# light.net
KiCad netlist of a schematic drawn in EAGLE
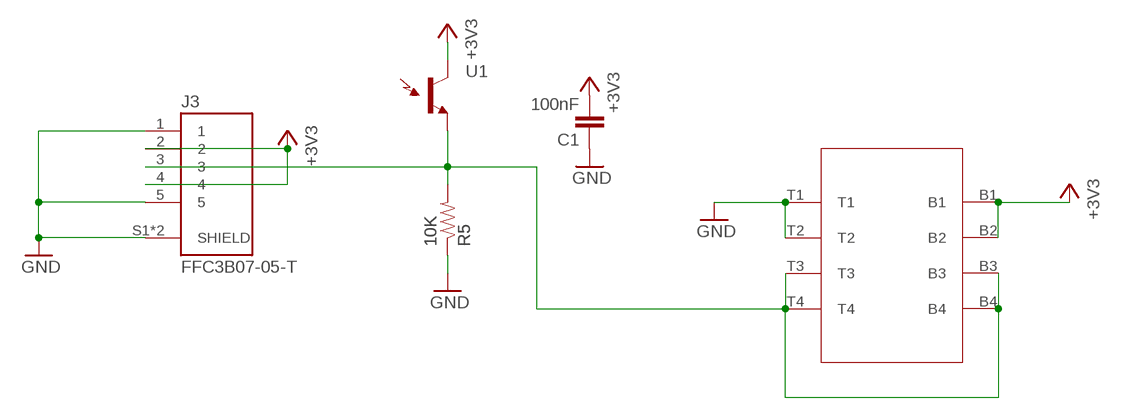
[diagram p0: schematic, sheet 1]

(export (version "E")
  (design (tool "Eeschema 10.0.6"))
  (components
    (comp (ref "C1")
      (value "100nF")
      (footprint "eagle-import:0805")
      (libsource (lib "eagle-import") (part "CAP0805"))
    )
    (comp (ref "J3")
      (value "FFC3B07-05-T")
      (footprint "eagle-import:GCT_FFC3B07-05-T")
      (fields (field (name "MF") "Global Connector Technology"))
      (libsource (lib "eagle-import") (part "FFC3B07-05-T"))
    )
    (comp (ref "R5")
      (value "10K")
      (footprint "eagle-import:0805")
      (libsource (lib "eagle-import") (part "RESISTOR0805-RES"))
    )
    (comp (ref "U$1")
      (value "LS_VERT")
      (footprint "eagle-import:LS_VERT")
      (libsource (lib "eagle-import") (part "LS_VERT"))
    )
    (comp (ref "U1")
      (value "TEMT6000")
      (footprint "eagle-import:TEMT6000-SEN")
      (libsource (lib "eagle-import") (part "TEMT6000"))
    )
  )
  (nets
    (net (code "1") (name "+3V3") (class "Default")
      (node (ref "C1") (pin "2") (pinfunction "2_2") (pintype "passive"))
      (node (ref "J3") (pin "2") (pinfunction "2_2") (pintype "passive"))
      (node (ref "J3") (pin "4") (pinfunction "4_4") (pintype "passive"))
      (node (ref "U$1") (pin "B1") (pinfunction "B1_B1") (pintype "bidirectional"))
      (node (ref "U$1") (pin "B2") (pinfunction "B2_B2") (pintype "bidirectional"))
      (node (ref "U1") (pin "COLLECTOR") (pinfunction "C1_COLLECTOR") (pintype "passive"))
    )
    (net (code "2") (name "GND") (class "Default")
      (node (ref "C1") (pin "1") (pinfunction "1_1") (pintype "passive"))
      (node (ref "J3") (pin "1") (pinfunction "1_1") (pintype "passive"))
      (node (ref "J3") (pin "5") (pinfunction "5_5") (pintype "passive"))
      (node (ref "J3") (pin "S1") (pinfunction "SHIELD_S1") (pintype "passive"))
      (node (ref "J3") (pin "S2") (pinfunction "SHIELD_S2") (pintype "passive"))
      (node (ref "R5") (pin "1") (pinfunction "1_1") (pintype "passive"))
      (node (ref "U$1") (pin "T1") (pinfunction "T1_T1") (pintype "bidirectional"))
      (node (ref "U$1") (pin "T2") (pinfunction "T2_T2") (pintype "bidirectional"))
    )
    (net (code "3") (name "Net-(U1-E1)") (class "Default")
      (node (ref "J3") (pin "3") (pinfunction "3_3") (pintype "passive"))
      (node (ref "R5") (pin "2") (pinfunction "2_2") (pintype "passive"))
      (node (ref "U$1") (pin "B3") (pinfunction "B3_B3") (pintype "bidirectional"))
      (node (ref "U$1") (pin "B4") (pinfunction "B4_B4") (pintype "bidirectional"))
      (node (ref "U$1") (pin "T3") (pinfunction "T3_T3") (pintype "bidirectional"))
      (node (ref "U$1") (pin "T4") (pinfunction "T4_T4") (pintype "bidirectional"))
      (node (ref "U1") (pin "EMITTER") (pinfunction "E1_EMITTER") (pintype "passive"))
    )
  )
)
